# 3_IIP_QuadUART.net
KiCad netlist of a schematic drawn in Altium Designer
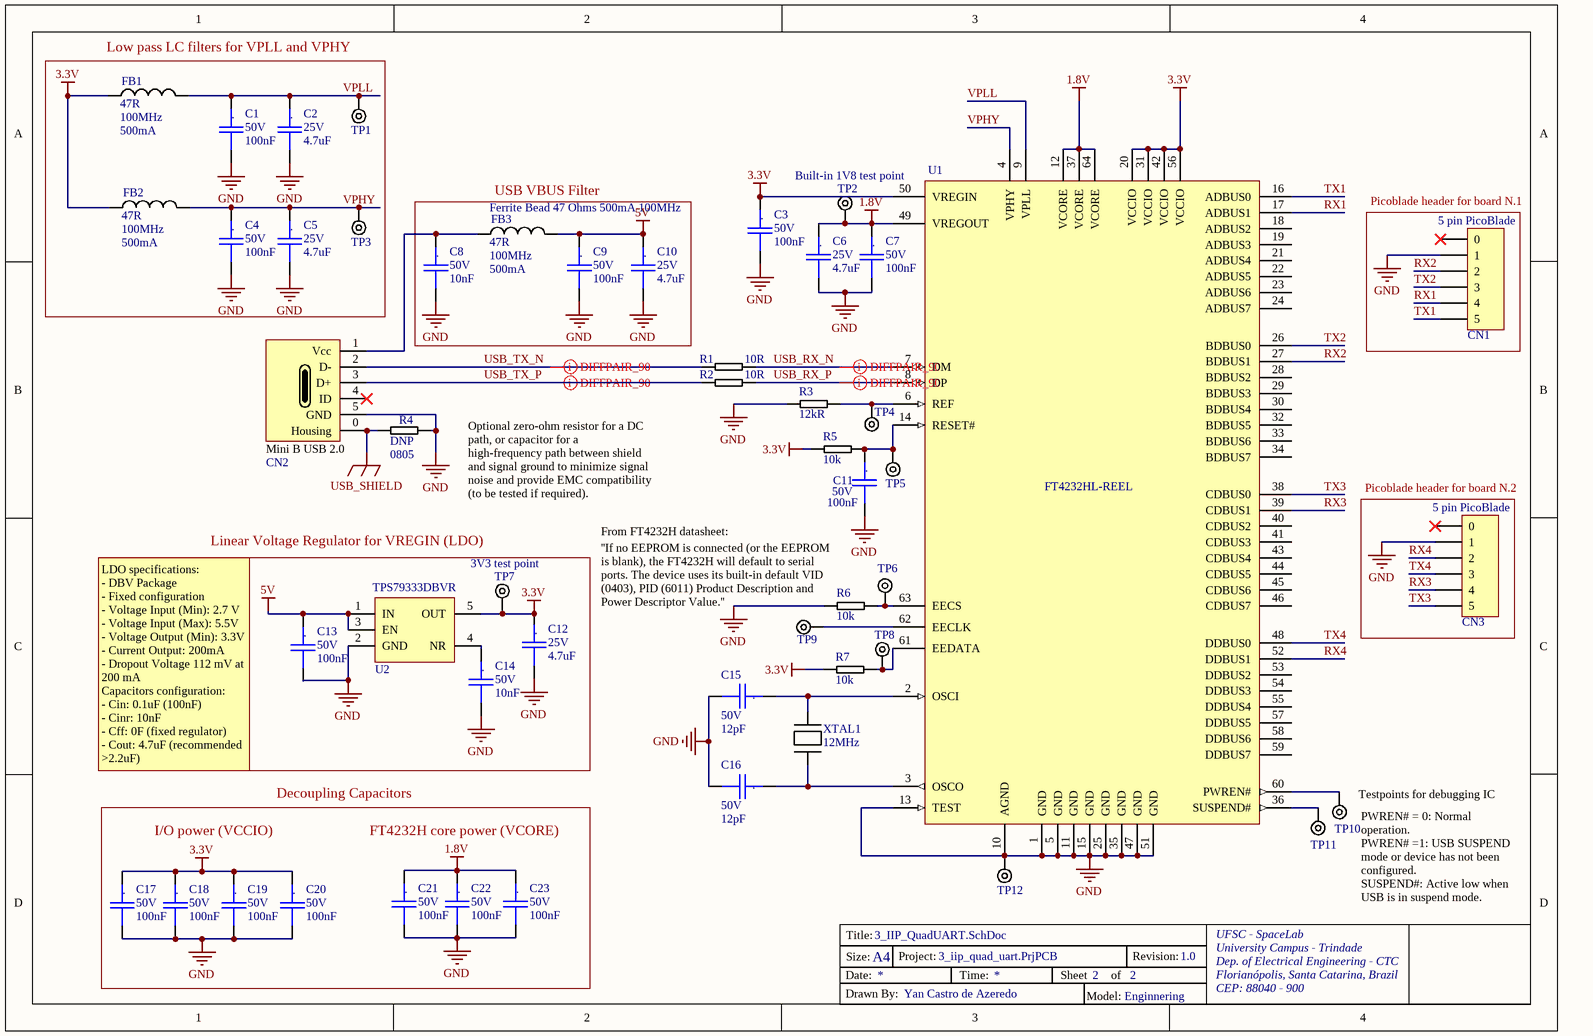
[diagram p0: 3_IIP_QuadUART.SchDoc]

(export (version "E")
  (design (tool "Eeschema 10.0.6"))
  (components
    (comp (ref "C1")
      (value "0.1 uF, 0603 (1608 metric)")
      (footprint "C0603_MD")
      (fields
        (field (name "MANUFACTURER") "TDK")
        (field (name "TOLERANCE") "10%")
        (field (name "VOLTAGE") "50V")
        (field (name "VOLTAGE RATING") "50V")
        (field (name "CAPACITANCE") "100nF")
      )
      (libsource (lib "IB_floripasat2") (part "C1608X7R1H104K080AA"))
    )
    (comp (ref "C2")
      (value "4.7 uF, 0802 (2012 metric)")
      (footprint "C0805_MD")
      (description "Ceramic Capacitor SMD Multilayer, 0805 [2012 Metric], 4.7 uF, 25 V,  10%, X7R, C Series")
      (fields
        (field (name "MANUFACTURER") "TDK")
        (field (name "TOLERANCE") "10%")
        (field (name "VOLTAGE RATING") "25V")
        (field (name "CAPACITANCE") "4.7uF")
      )
      (libsource (lib "IB_floripasat2") (part "C2012X7R1E475K125AB"))
    )
    (comp (ref "C3")
      (value "0.1 uF, 0603 (1608 metric)")
      (footprint "C0603_MD")
      (fields
        (field (name "MANUFACTURER") "TDK")
        (field (name "TOLERANCE") "10%")
        (field (name "VOLTAGE") "50V")
        (field (name "VOLTAGE RATING") "50V")
        (field (name "CAPACITANCE") "100nF")
      )
      (libsource (lib "IB_floripasat2") (part "C1608X7R1H104K080AA"))
    )
    (comp (ref "C4")
      (value "0.1 uF, 0603 (1608 metric)")
      (footprint "C0603_MD")
      (fields
        (field (name "MANUFACTURER") "TDK")
        (field (name "TOLERANCE") "10%")
        (field (name "VOLTAGE") "50V")
        (field (name "VOLTAGE RATING") "50V")
        (field (name "CAPACITANCE") "100nF")
      )
      (libsource (lib "IB_floripasat2") (part "C1608X7R1H104K080AA"))
    )
    (comp (ref "C5")
      (value "4.7 uF, 0802 (2012 metric)")
      (footprint "C0805_MD")
      (description "Ceramic Capacitor SMD Multilayer, 0805 [2012 Metric], 4.7 uF, 25 V,  10%, X7R, C Series")
      (fields
        (field (name "MANUFACTURER") "TDK")
        (field (name "TOLERANCE") "10%")
        (field (name "VOLTAGE RATING") "25V")
        (field (name "CAPACITANCE") "4.7uF")
      )
      (libsource (lib "IB_floripasat2") (part "C2012X7R1E475K125AB"))
    )
    (comp (ref "C6")
      (value "4.7 uF, 0802 (2012 metric)")
      (footprint "C0805_MD")
      (description "Ceramic Capacitor SMD Multilayer, 0805 [2012 Metric], 4.7 uF, 25 V,  10%, X7R, C Series")
      (fields
        (field (name "MANUFACTURER") "TDK")
        (field (name "TOLERANCE") "10%")
        (field (name "VOLTAGE RATING") "25V")
        (field (name "CAPACITANCE") "4.7uF")
      )
      (libsource (lib "IB_floripasat2") (part "C2012X7R1E475K125AB"))
    )
    (comp (ref "C7")
      (value "0.1 uF, 0603 (1608 metric)")
      (footprint "C0603_MD")
      (fields
        (field (name "MANUFACTURER") "TDK")
        (field (name "TOLERANCE") "10%")
        (field (name "VOLTAGE") "50V")
        (field (name "VOLTAGE RATING") "50V")
        (field (name "CAPACITANCE") "100nF")
      )
      (libsource (lib "IB_floripasat2") (part "C1608X7R1H104K080AA"))
    )
    (comp (ref "C8")
      (value "10000 pF, 0805 (2012 metric)")
      (footprint "C0805_MD")
      (fields
        (field (name "MANUFACTURER") "Kyocera AVX")
        (field (name "TOLERANCE") "10%")
        (field (name "MANUFACTURER PART NUMBER") "08055C103KAT4A")
        (field (name "VOLTAGE") "50V")
        (field (name "CAPACITANCE") "10nF")
      )
      (libsource (lib "IB_floripasat2") (part "08055C103KAT4A"))
    )
    (comp (ref "C9")
      (value "0.1 uF, 0603 (1608 metric)")
      (footprint "C0603_MD")
      (fields
        (field (name "MANUFACTURER") "TDK")
        (field (name "TOLERANCE") "10%")
        (field (name "VOLTAGE") "50V")
        (field (name "VOLTAGE RATING") "50V")
        (field (name "CAPACITANCE") "100nF")
      )
      (libsource (lib "IB_floripasat2") (part "C1608X7R1H104K080AA"))
    )
    (comp (ref "C10")
      (value "4.7 uF, 0802 (2012 metric)")
      (footprint "C0805_MD")
      (description "Ceramic Capacitor SMD Multilayer, 0805 [2012 Metric], 4.7 uF, 25 V,  10%, X7R, C Series")
      (fields
        (field (name "MANUFACTURER") "TDK")
        (field (name "TOLERANCE") "10%")
        (field (name "VOLTAGE RATING") "25V")
        (field (name "CAPACITANCE") "4.7uF")
      )
      (libsource (lib "IB_floripasat2") (part "C2012X7R1E475K125AB"))
    )
    (comp (ref "C11")
      (value "0.1 uF, 0603 (1608 metric)")
      (footprint "C0603_MD")
      (fields
        (field (name "MANUFACTURER") "TDK")
        (field (name "TOLERANCE") "10%")
        (field (name "VOLTAGE") "50V")
        (field (name "VOLTAGE RATING") "50V")
        (field (name "CAPACITANCE") "100nF")
      )
      (libsource (lib "IB_floripasat2") (part "C1608X7R1H104K080AA"))
    )
    (comp (ref "C12")
      (value "4.7 uF, 0802 (2012 metric)")
      (footprint "C0805_MD")
      (description "Ceramic Capacitor SMD Multilayer, 0805 [2012 Metric], 4.7 uF, 25 V,  10%, X7R, C Series")
      (fields
        (field (name "MANUFACTURER") "TDK")
        (field (name "TOLERANCE") "10%")
        (field (name "VOLTAGE RATING") "25V")
        (field (name "CAPACITANCE") "4.7uF")
      )
      (libsource (lib "IB_floripasat2") (part "C2012X7R1E475K125AB"))
    )
    (comp (ref "C13")
      (value "0.1 uF, 0603 (1608 metric)")
      (footprint "C0603_MD")
      (fields
        (field (name "MANUFACTURER") "TDK")
        (field (name "TOLERANCE") "10%")
        (field (name "VOLTAGE") "50V")
        (field (name "VOLTAGE RATING") "50V")
        (field (name "CAPACITANCE") "100nF")
      )
      (libsource (lib "IB_floripasat2") (part "C1608X7R1H104K080AA"))
    )
    (comp (ref "C14")
      (value "10000 pF, 0805 (2012 metric)")
      (footprint "C0805_MD")
      (fields
        (field (name "MANUFACTURER") "Kyocera AVX")
        (field (name "TOLERANCE") "10%")
        (field (name "MANUFACTURER PART NUMBER") "08055C103KAT4A")
        (field (name "VOLTAGE") "50V")
        (field (name "CAPACITANCE") "10nF")
      )
      (libsource (lib "IB_floripasat2") (part "08055C103KAT4A"))
    )
    (comp (ref "C15")
      (value "12 pF, 0603 (1608 metric)")
      (footprint "C0603_MD")
      (description "Cap Ceramic 12pF 50VDC C0G 5% SMD 0603 Paper T/R")
      (fields
        (field (name "MANUFACTURER") "Samsung")
        (field (name "MANUFACTURER PART NUMBER") "CL10C120JB8NNNC")
        (field (name "VOLTAGE") "50V")
        (field (name "CAPACITANCE") "12pF")
      )
      (libsource (lib "IB_floripasat2") (part "CL10C120JB8NNNC"))
    )
    (comp (ref "C16")
      (value "12 pF, 0603 (1608 metric)")
      (footprint "C0603_MD")
      (description "Cap Ceramic 12pF 50VDC C0G 5% SMD 0603 Paper T/R")
      (fields
        (field (name "MANUFACTURER") "Samsung")
        (field (name "MANUFACTURER PART NUMBER") "CL10C120JB8NNNC")
        (field (name "VOLTAGE") "50V")
        (field (name "CAPACITANCE") "12pF")
      )
      (libsource (lib "IB_floripasat2") (part "CL10C120JB8NNNC"))
    )
    (comp (ref "C17")
      (value "0.1 uF, 0603 (1608 metric)")
      (footprint "C0603_MD")
      (fields
        (field (name "MANUFACTURER") "TDK")
        (field (name "TOLERANCE") "10%")
        (field (name "VOLTAGE") "50V")
        (field (name "VOLTAGE RATING") "50V")
        (field (name "CAPACITANCE") "100nF")
      )
      (libsource (lib "IB_floripasat2") (part "C1608X7R1H104K080AA"))
    )
    (comp (ref "C18")
      (value "0.1 uF, 0603 (1608 metric)")
      (footprint "C0603_MD")
      (fields
        (field (name "MANUFACTURER") "TDK")
        (field (name "TOLERANCE") "10%")
        (field (name "VOLTAGE") "50V")
        (field (name "VOLTAGE RATING") "50V")
        (field (name "CAPACITANCE") "100nF")
      )
      (libsource (lib "IB_floripasat2") (part "C1608X7R1H104K080AA"))
    )
    (comp (ref "C19")
      (value "0.1 uF, 0603 (1608 metric)")
      (footprint "C0603_MD")
      (fields
        (field (name "MANUFACTURER") "TDK")
        (field (name "TOLERANCE") "10%")
        (field (name "VOLTAGE") "50V")
        (field (name "VOLTAGE RATING") "50V")
        (field (name "CAPACITANCE") "100nF")
      )
      (libsource (lib "IB_floripasat2") (part "C1608X7R1H104K080AA"))
    )
    (comp (ref "C20")
      (value "0.1 uF, 0603 (1608 metric)")
      (footprint "C0603_MD")
      (fields
        (field (name "MANUFACTURER") "TDK")
        (field (name "TOLERANCE") "10%")
        (field (name "VOLTAGE") "50V")
        (field (name "VOLTAGE RATING") "50V")
        (field (name "CAPACITANCE") "100nF")
      )
      (libsource (lib "IB_floripasat2") (part "C1608X7R1H104K080AA"))
    )
    (comp (ref "C21")
      (value "0.1 uF, 0603 (1608 metric)")
      (footprint "C0603_MD")
      (fields
        (field (name "MANUFACTURER") "TDK")
        (field (name "TOLERANCE") "10%")
        (field (name "VOLTAGE") "50V")
        (field (name "VOLTAGE RATING") "50V")
        (field (name "CAPACITANCE") "100nF")
      )
      (libsource (lib "IB_floripasat2") (part "C1608X7R1H104K080AA"))
    )
    (comp (ref "C22")
      (value "0.1 uF, 0603 (1608 metric)")
      (footprint "C0603_MD")
      (fields
        (field (name "MANUFACTURER") "TDK")
        (field (name "TOLERANCE") "10%")
        (field (name "VOLTAGE") "50V")
        (field (name "VOLTAGE RATING") "50V")
        (field (name "CAPACITANCE") "100nF")
      )
      (libsource (lib "IB_floripasat2") (part "C1608X7R1H104K080AA"))
    )
    (comp (ref "C23")
      (value "0.1 uF, 0603 (1608 metric)")
      (footprint "C0603_MD")
      (fields
        (field (name "MANUFACTURER") "TDK")
        (field (name "TOLERANCE") "10%")
        (field (name "VOLTAGE") "50V")
        (field (name "VOLTAGE RATING") "50V")
        (field (name "CAPACITANCE") "100nF")
      )
      (libsource (lib "IB_floripasat2") (part "C1608X7R1H104K080AA"))
    )
    (comp (ref "CN1")
      (value "5 pin PicoBlade")
      (footprint "PICO BLADE 0533980571")
      (description "Wire-To-Board Connector, Vertical, PicoBlade 53398 Series, Surface Mount, Header, 5, 1.25 mm")
      (fields (field (name "MANUFACTURER") "Molex") (field (name "MANUFACTURER PART NUMBER") "53398-0571"))
      (libsource (lib "IB_floripasat2") (part "53398-0571"))
    )
    (comp (ref "CN2")
      (value "Vertical mini B USB 2.0 port")
      (footprint "MINI USB B 180GRAUS WE")
      (fields
        (field (name "MANUFACTURER") "Wurth Electronics")
        (field (name "MANUFACTURER PART NUMBER") "651005136421")
      )
      (libsource (lib "IB_floripasat2") (part "651005136421"))
    )
    (comp (ref "CN3")
      (value "5 pin PicoBlade")
      (footprint "PICO BLADE 0533980571")
      (description "Wire-To-Board Connector, Vertical, PicoBlade 53398 Series, Surface Mount, Header, 5, 1.25 mm")
      (fields (field (name "MANUFACTURER") "Molex") (field (name "MANUFACTURER PART NUMBER") "53398-0571"))
      (libsource (lib "IB_floripasat2") (part "53398-0571"))
    )
    (comp (ref "FB1")
      (value "Ferrite Bead 47 Ohms 500mA 100MHz")
      (footprint "L0603")
      (description "WURTH ELEKTRONIK   742792608   FERRITE BEAD, 0.1 OHM, 0.5A, 0603")
      (fields
        (field (name "MANUFACTURER") "Wurth Electronics")
        (field (name "TOLERANCE") "25%")
        (field (name "IMPEDANCE") "47R")
        (field (name "TEST FREQUENCY") "100MHz")
        (field (name "CURRENT RATING") "500mA")
      )
      (libsource (lib "IB_floripasat2") (part "742792608"))
    )
    (comp (ref "FB2")
      (value "Ferrite Bead 47 Ohms 500mA 100MHz")
      (footprint "L0603")
      (description "WURTH ELEKTRONIK   742792608   FERRITE BEAD, 0.1 OHM, 0.5A, 0603")
      (fields
        (field (name "MANUFACTURER") "Wurth Electronics")
        (field (name "TOLERANCE") "25%")
        (field (name "IMPEDANCE") "47R")
        (field (name "TEST FREQUENCY") "100MHz")
        (field (name "CURRENT RATING") "500mA")
      )
      (libsource (lib "IB_floripasat2") (part "742792608"))
    )
    (comp (ref "FB3")
      (value "Ferrite Bead 47 Ohms 500mA 100MHz")
      (footprint "L0603")
      (description "WURTH ELEKTRONIK   742792608   FERRITE BEAD, 0.1 OHM, 0.5A, 0603")
      (fields
        (field (name "MANUFACTURER") "Wurth Electronics")
        (field (name "TOLERANCE") "25%")
        (field (name "IMPEDANCE") "47R")
        (field (name "TEST FREQUENCY") "100MHz")
        (field (name "CURRENT RATING") "500mA")
      )
      (libsource (lib "IB_floripasat2") (part "742792608"))
    )
    (comp (ref "R1")
      (value "RES 10 ohms (0603)")
      (footprint "R0603_MD")
      (description "YAGEO (PHYCOMP) - RC0603FR-0710RL - RES, THICK FILM, 10R, 1%, 0.1W, 0603")
      (fields
        (field (name "MANUFACTURER") "Yageo")
        (field (name "TOLERANCE") "1%")
        (field (name "RESISTANCE") "10R")
      )
      (libsource (lib "IB_floripasat2") (part "RC0603FR-0710RL"))
    )
    (comp (ref "R2")
      (value "RES 10 ohms (0603)")
      (footprint "R0603_MD")
      (description "YAGEO (PHYCOMP) - RC0603FR-0710RL - RES, THICK FILM, 10R, 1%, 0.1W, 0603")
      (fields
        (field (name "MANUFACTURER") "Yageo")
        (field (name "TOLERANCE") "1%")
        (field (name "RESISTANCE") "10R")
      )
      (libsource (lib "IB_floripasat2") (part "RC0603FR-0710RL"))
    )
    (comp (ref "R3")
      (value "RES 12K ohms (0805)")
      (footprint "R0805_MD")
      (description "Resistor, SMT, 0805, 12K Ohm, +/-1%, +/-100ppm, Thk Film, T/R Marked")
      (fields
        (field (name "MANUFACTURER") "Stackpole Electronics")
        (field (name "MANUFACTURER PART NUMBER") "RMCF0805FT12K0")
        (field (name "RESISTANCE") "12kR")
      )
      (libsource (lib "IB_floripasat2") (part "RMCF0805FT12K0"))
    )
    (comp (ref "R4")
      (value "DNP")
      (footprint "R0805_MD")
      (fields
        (field (name "MANUFACTURER") "Vishay")
        (field (name "TOLERANCE") "1%")
        (field (name "MANUFACTURER PART NUMBER") "CRCW08050000Z0EA")
        (field (name "CASE/PACKAGE") "0805")
      )
      (libsource (lib "IB_floripasat2") (part "CRCW08050000Z0EA"))
    )
    (comp (ref "R5")
      (value "10k")
      (footprint "R0805_MD")
      (description "RES 10.0K OHM 1/8W 1% 0805 SMD")
      (fields (field (name "MANUFACTURER") "Vishay Dale") (field (name "TOLERANCE") "1%"))
      (libsource (lib "IB_floripasat2") (part "CRCW080510K0FKEA"))
    )
    (comp (ref "R6")
      (value "10k")
      (footprint "R0805_MD")
      (description "RES 10.0K OHM 1/8W 1% 0805 SMD")
      (fields (field (name "MANUFACTURER") "Vishay Dale") (field (name "TOLERANCE") "1%"))
      (libsource (lib "IB_floripasat2") (part "CRCW080510K0FKEA"))
    )
    (comp (ref "R7")
      (value "10k")
      (footprint "R0805_MD")
      (description "RES 10.0K OHM 1/8W 1% 0805 SMD")
      (fields (field (name "MANUFACTURER") "Vishay Dale") (field (name "TOLERANCE") "1%"))
      (libsource (lib "IB_floripasat2") (part "CRCW080510K0FKEA"))
    )
    (comp (ref "TP1")
      (value "DNP")
      (footprint "TEST POINT PTH")
      (description "TEST POINT PAD")
      (libsource (lib "IB_floripasat2") (part "Test Point PTH"))
    )
    (comp (ref "TP2")
      (value "DNP")
      (footprint "TEST POINT PTH")
      (description "TEST POINT PAD")
      (libsource (lib "IB_floripasat2") (part "Test Point PTH"))
    )
    (comp (ref "TP3")
      (value "DNP")
      (footprint "TEST POINT PTH")
      (description "TEST POINT PAD")
      (libsource (lib "IB_floripasat2") (part "Test Point PTH"))
    )
    (comp (ref "TP4")
      (value "DNP")
      (footprint "TEST POINT PTH")
      (description "TEST POINT PAD")
      (libsource (lib "IB_floripasat2") (part "Test Point PTH"))
    )
    (comp (ref "TP5")
      (value "DNP")
      (footprint "TEST POINT PTH")
      (description "TEST POINT PAD")
      (libsource (lib "IB_floripasat2") (part "Test Point PTH"))
    )
    (comp (ref "TP6")
      (value "DNP")
      (footprint "TEST POINT PTH")
      (description "TEST POINT PAD")
      (libsource (lib "IB_floripasat2") (part "Test Point PTH"))
    )
    (comp (ref "TP7")
      (value "DNP")
      (footprint "TEST POINT PTH")
      (description "TEST POINT PAD")
      (libsource (lib "IB_floripasat2") (part "Test Point PTH"))
    )
    (comp (ref "TP8")
      (value "DNP")
      (footprint "TEST POINT PTH")
      (description "TEST POINT PAD")
      (libsource (lib "IB_floripasat2") (part "Test Point PTH"))
    )
    (comp (ref "TP9")
      (value "DNP")
      (footprint "TEST POINT PTH")
      (description "TEST POINT PAD")
      (libsource (lib "IB_floripasat2") (part "Test Point PTH"))
    )
    (comp (ref "TP10")
      (value "DNP")
      (footprint "TEST POINT PTH")
      (description "TEST POINT PAD")
      (libsource (lib "IB_floripasat2") (part "Test Point PTH"))
    )
    (comp (ref "TP11")
      (value "DNP")
      (footprint "TEST POINT PTH")
      (description "TEST POINT PAD")
      (libsource (lib "IB_floripasat2") (part "Test Point PTH"))
    )
    (comp (ref "TP12")
      (value "DNP")
      (footprint "TEST POINT PTH")
      (description "TEST POINT PAD")
      (libsource (lib "IB_floripasat2") (part "Test Point PTH"))
    )
    (comp (ref "U1")
      (value "FT4232HL-REEL")
      (footprint "LQFP-64")
      (description "FTDI - FT4232HL-REEL - USB-UART/MPSSE, 4232, QUAD, 64LQFP")
      (fields (field (name "MANUFACTURER") "FTDI"))
      (libsource (lib "IB_floripasat2") (part "FT4232HL-REEL"))
    )
    (comp (ref "U2")
      (value "TPS79333DBVR")
      (footprint "SOT23-5")
      (description "TEXAS INSTRUMENTS - TPS79333DBVR - IC, V REG, LINEAR, 0.2A, SOT-23-5")
      (fields (field (name "MANUFACTURER") "Texas Instruments"))
      (libsource (lib "IB_floripasat2") (part "TPS79333DBVR"))
    )
    (comp (ref "XTAL1")
      (value "12.000MHz 12pF")
      (footprint "TXC 7A Series")
      (description "Crystals 12.000MHz 30ppm 12pF -40C to 85C")
      (fields
        (field (name "MANUFACTURER") "TXC")
        (field (name "TOLERANCE") "30ppm")
        (field (name "FREQUENCY") "12MHz")
      )
      (libsource (lib "IB_floripasat2") (part "AA-12.000MAGE-T"))
    )
  )
  (nets
    (net (code "1") (name "/RX1") (class "Default")
      (node (ref "CN1") (pin "4") (pinfunction "4_4") (pintype "passive"))
      (node (ref "U1") (pin "17") (pinfunction "ADBUS1_17") (pintype "passive"))
    )
    (net (code "2") (name "/RX2") (class "Default")
      (node (ref "CN1") (pin "2") (pinfunction "2_2") (pintype "passive"))
      (node (ref "U1") (pin "27") (pinfunction "BDBUS1_27") (pintype "passive"))
    )
    (net (code "3") (name "/RX3") (class "Default")
      (node (ref "CN3") (pin "4") (pinfunction "4_4") (pintype "passive"))
      (node (ref "U1") (pin "39") (pinfunction "CDBUS1_39") (pintype "passive"))
    )
    (net (code "4") (name "/RX4") (class "Default")
      (node (ref "CN3") (pin "2") (pinfunction "2_2") (pintype "passive"))
      (node (ref "U1") (pin "52") (pinfunction "DDBUS1_52") (pintype "passive"))
    )
    (net (code "5") (name "/TX1") (class "Default")
      (node (ref "CN1") (pin "5") (pinfunction "5_5") (pintype "passive"))
      (node (ref "U1") (pin "16") (pinfunction "ADBUS0_16") (pintype "passive"))
    )
    (net (code "6") (name "/TX2") (class "Default")
      (node (ref "CN1") (pin "3") (pinfunction "3_3") (pintype "passive"))
      (node (ref "U1") (pin "26") (pinfunction "BDBUS0_26") (pintype "passive"))
    )
    (net (code "7") (name "/TX3") (class "Default")
      (node (ref "CN3") (pin "5") (pinfunction "5_5") (pintype "passive"))
      (node (ref "U1") (pin "38") (pinfunction "CDBUS0_38") (pintype "passive"))
    )
    (net (code "8") (name "/TX4") (class "Default")
      (node (ref "CN3") (pin "3") (pinfunction "3_3") (pintype "passive"))
      (node (ref "U1") (pin "48") (pinfunction "DDBUS0_48") (pintype "passive"))
    )
    (net (code "9") (name "/USB_RX_N") (class "Default")
      (node (ref "R1") (pin "2") (pinfunction "2_2") (pintype "passive"))
      (node (ref "U1") (pin "7") (pinfunction "DM_7") (pintype "bidirectional"))
    )
    (net (code "10") (name "/USB_RX_P") (class "Default")
      (node (ref "R2") (pin "2") (pinfunction "2_2") (pintype "passive"))
      (node (ref "U1") (pin "8") (pinfunction "DP_8") (pintype "bidirectional"))
    )
    (net (code "11") (name "/USB_TX_N") (class "Default")
      (node (ref "CN2") (pin "2") (pinfunction "D-_2") (pintype "passive"))
      (node (ref "R1") (pin "1") (pinfunction "1_1") (pintype "passive"))
    )
    (net (code "12") (name "/USB_TX_P") (class "Default")
      (node (ref "CN2") (pin "3") (pinfunction "D+_3") (pintype "passive"))
      (node (ref "R2") (pin "1") (pinfunction "1_1") (pintype "passive"))
    )
    (net (code "13") (name "/VPHY") (class "Default")
      (node (ref "C4") (pin "1") (pinfunction "1_1") (pintype "passive"))
      (node (ref "C5") (pin "1") (pinfunction "1_1") (pintype "passive"))
      (node (ref "FB2") (pin "2") (pinfunction "2_2") (pintype "passive"))
      (node (ref "TP3") (pin "1") (pinfunction "1_1") (pintype "passive"))
      (node (ref "U1") (pin "4") (pinfunction "VPHY_4") (pintype "power_in"))
    )
    (net (code "14") (name "/VPLL") (class "Default")
      (node (ref "C1") (pin "1") (pinfunction "1_1") (pintype "passive"))
      (node (ref "C2") (pin "1") (pinfunction "1_1") (pintype "passive"))
      (node (ref "FB1") (pin "2") (pinfunction "2_2") (pintype "passive"))
      (node (ref "TP1") (pin "1") (pinfunction "1_1") (pintype "passive"))
      (node (ref "U1") (pin "9") (pinfunction "VPLL_9") (pintype "power_in"))
    )
    (net (code "15") (name "1.8V") (class "Default")
      (node (ref "C21") (pin "1") (pinfunction "1_1") (pintype "passive"))
      (node (ref "C22") (pin "1") (pinfunction "1_1") (pintype "passive"))
      (node (ref "C23") (pin "1") (pinfunction "1_1") (pintype "passive"))
      (node (ref "C6") (pin "1") (pinfunction "1_1") (pintype "passive"))
      (node (ref "C7") (pin "1") (pinfunction "1_1") (pintype "passive"))
      (node (ref "TP2") (pin "1") (pinfunction "1_1") (pintype "passive"))
      (node (ref "U1") (pin "12") (pinfunction "VCORE_12") (pintype "power_in"))
      (node (ref "U1") (pin "37") (pinfunction "VCORE_37") (pintype "power_in"))
      (node (ref "U1") (pin "49") (pinfunction "VREGOUT_49") (pintype "passive"))
      (node (ref "U1") (pin "64") (pinfunction "VCORE_64") (pintype "power_in"))
    )
    (net (code "16") (name "3.3V") (class "Default")
      (node (ref "C12") (pin "1") (pinfunction "1_1") (pintype "passive"))
      (node (ref "C17") (pin "1") (pinfunction "1_1") (pintype "passive"))
      (node (ref "C18") (pin "1") (pinfunction "1_1") (pintype "passive"))
      (node (ref "C19") (pin "1") (pinfunction "1_1") (pintype "passive"))
      (node (ref "C20") (pin "1") (pinfunction "1_1") (pintype "passive"))
      (node (ref "C3") (pin "1") (pinfunction "1_1") (pintype "passive"))
      (node (ref "FB1") (pin "1") (pinfunction "1_1") (pintype "passive"))
      (node (ref "FB2") (pin "1") (pinfunction "1_1") (pintype "passive"))
      (node (ref "R5") (pin "1") (pinfunction "1_1") (pintype "passive"))
      (node (ref "R7") (pin "1") (pinfunction "1_1") (pintype "passive"))
      (node (ref "TP7") (pin "1") (pinfunction "1_1") (pintype "passive"))
      (node (ref "U1") (pin "20") (pinfunction "VCCIO_20") (pintype "power_in"))
      (node (ref "U1") (pin "31") (pinfunction "VCCIO_31") (pintype "power_in"))
      (node (ref "U1") (pin "42") (pinfunction "VCCIO_42") (pintype "power_in"))
      (node (ref "U1") (pin "50") (pinfunction "VREGIN_50") (pintype "passive"))
      (node (ref "U1") (pin "56") (pinfunction "VCCIO_56") (pintype "power_in"))
      (node (ref "U2") (pin "5") (pinfunction "OUT_5") (pintype "passive"))
    )
    (net (code "17") (name "5V") (class "Default")
      (node (ref "C10") (pin "1") (pinfunction "1_1") (pintype "passive"))
      (node (ref "C13") (pin "1") (pinfunction "1_1") (pintype "passive"))
      (node (ref "C9") (pin "1") (pinfunction "1_1") (pintype "passive"))
      (node (ref "FB3") (pin "2") (pinfunction "2_2") (pintype "passive"))
      (node (ref "U2") (pin "1") (pinfunction "IN_1") (pintype "passive"))
      (node (ref "U2") (pin "3") (pinfunction "EN_3") (pintype "passive"))
    )
    (net (code "18") (name "GND") (class "Default")
      (node (ref "C1") (pin "2") (pinfunction "2_2") (pintype "passive"))
      (node (ref "C10") (pin "2") (pinfunction "2_2") (pintype "passive"))
      (node (ref "C11") (pin "2") (pinfunction "2_2") (pintype "passive"))
      (node (ref "C12") (pin "2") (pinfunction "2_2") (pintype "passive"))
      (node (ref "C13") (pin "2") (pinfunction "2_2") (pintype "passive"))
      (node (ref "C14") (pin "2") (pinfunction "2_2") (pintype "passive"))
      (node (ref "C15") (pin "2") (pinfunction "2_2") (pintype "passive"))
      (node (ref "C16") (pin "2") (pinfunction "2_2") (pintype "passive"))
      (node (ref "C17") (pin "2") (pinfunction "2_2") (pintype "passive"))
      (node (ref "C18") (pin "2") (pinfunction "2_2") (pintype "passive"))
      (node (ref "C19") (pin "2") (pinfunction "2_2") (pintype "passive"))
      (node (ref "C2") (pin "2") (pinfunction "2_2") (pintype "passive"))
      (node (ref "C20") (pin "2") (pinfunction "2_2") (pintype "passive"))
      (node (ref "C21") (pin "2") (pinfunction "2_2") (pintype "passive"))
      (node (ref "C22") (pin "2") (pinfunction "2_2") (pintype "passive"))
      (node (ref "C23") (pin "2") (pinfunction "2_2") (pintype "passive"))
      (node (ref "C3") (pin "2") (pinfunction "2_2") (pintype "passive"))
      (node (ref "C4") (pin "2") (pinfunction "2_2") (pintype "passive"))
      (node (ref "C5") (pin "2") (pinfunction "2_2") (pintype "passive"))
      (node (ref "C6") (pin "2") (pinfunction "2_2") (pintype "passive"))
      (node (ref "C7") (pin "2") (pinfunction "2_2") (pintype "passive"))
      (node (ref "C8") (pin "2") (pinfunction "2_2") (pintype "passive"))
      (node (ref "C9") (pin "2") (pinfunction "2_2") (pintype "passive"))
      (node (ref "CN1") (pin "1") (pinfunction "1_1") (pintype "passive"))
      (node (ref "CN2") (pin "5") (pinfunction "GND_5") (pintype "passive"))
      (node (ref "CN3") (pin "1") (pinfunction "1_1") (pintype "passive"))
      (node (ref "R3") (pin "1") (pinfunction "1_1") (pintype "passive"))
      (node (ref "R4") (pin "2") (pinfunction "2_2") (pintype "passive"))
      (node (ref "R6") (pin "1") (pinfunction "1_1") (pintype "passive"))
      (node (ref "TP12") (pin "1") (pinfunction "1_1") (pintype "passive"))
      (node (ref "U1") (pin "1") (pinfunction "GND_1") (pintype "passive"))
      (node (ref "U1") (pin "10") (pinfunction "AGND_10") (pintype "passive"))
      (node (ref "U1") (pin "11") (pinfunction "GND_11") (pintype "passive"))
      (node (ref "U1") (pin "13") (pinfunction "TEST_13") (pintype "input"))
      (node (ref "U1") (pin "15") (pinfunction "GND_15") (pintype "passive"))
      (node (ref "U1") (pin "25") (pinfunction "GND_25") (pintype "passive"))
      (node (ref "U1") (pin "35") (pinfunction "GND_35") (pintype "passive"))
      (node (ref "U1") (pin "47") (pinfunction "GND_47") (pintype "passive"))
      (node (ref "U1") (pin "5") (pinfunction "GND_5") (pintype "passive"))
      (node (ref "U1") (pin "51") (pinfunction "GND_51") (pintype "passive"))
      (node (ref "U2") (pin "2") (pinfunction "GND_2") (pintype "passive"))
    )
    (net (code "19") (name "Net-(CN2-Vcc)") (class "Default")
      (node (ref "C8") (pin "1") (pinfunction "1_1") (pintype "passive"))
      (node (ref "CN2") (pin "1") (pinfunction "Vcc_1") (pintype "passive"))
      (node (ref "FB3") (pin "1") (pinfunction "1_1") (pintype "passive"))
    )
    (net (code "20") (name "Net-(U1-EECLK)") (class "Default")
      (node (ref "TP9") (pin "1") (pinfunction "1_1") (pintype "passive"))
      (node (ref "U1") (pin "62") (pinfunction "EECLK_62") (pintype "passive"))
    )
    (net (code "21") (name "Net-(U1-EECS)") (class "Default")
      (node (ref "R6") (pin "2") (pinfunction "2_2") (pintype "passive"))
      (node (ref "TP6") (pin "1") (pinfunction "1_1") (pintype "passive"))
      (node (ref "U1") (pin "63") (pinfunction "EECS_63") (pintype "passive"))
    )
    (net (code "22") (name "Net-(U1-EEDATA)") (class "Default")
      (node (ref "R7") (pin "2") (pinfunction "2_2") (pintype "passive"))
      (node (ref "TP8") (pin "1") (pinfunction "1_1") (pintype "passive"))
      (node (ref "U1") (pin "61") (pinfunction "EEDATA_61") (pintype "passive"))
    )
    (net (code "23") (name "Net-(U1-OSCI)") (class "Default")
      (node (ref "C15") (pin "1") (pinfunction "1_1") (pintype "passive"))
      (node (ref "U1") (pin "2") (pinfunction "OSCI_2") (pintype "input"))
      (node (ref "XTAL1") (pin "1") (pinfunction "1_1") (pintype "passive"))
    )
    (net (code "24") (name "Net-(U1-OSCO)") (class "Default")
      (node (ref "C16") (pin "1") (pinfunction "1_1") (pintype "passive"))
      (node (ref "U1") (pin "3") (pinfunction "OSCO_3") (pintype "output"))
      (node (ref "XTAL1") (pin "2") (pinfunction "2_2") (pintype "passive"))
    )
    (net (code "25") (name "Net-(U1-PWREN#)") (class "Default")
      (node (ref "TP10") (pin "1") (pinfunction "1_1") (pintype "passive"))
      (node (ref "U1") (pin "60") (pinfunction "PWREN#_60") (pintype "output"))
    )
    (net (code "26") (name "Net-(U1-REF)") (class "Default")
      (node (ref "R3") (pin "2") (pinfunction "2_2") (pintype "passive"))
      (node (ref "TP4") (pin "1") (pinfunction "1_1") (pintype "passive"))
      (node (ref "U1") (pin "6") (pinfunction "REF_6") (pintype "input"))
    )
    (net (code "27") (name "Net-(U1-RESET#)") (class "Default")
      (node (ref "C11") (pin "1") (pinfunction "1_1") (pintype "passive"))
      (node (ref "R5") (pin "2") (pinfunction "2_2") (pintype "passive"))
      (node (ref "TP5") (pin "1") (pinfunction "1_1") (pintype "passive"))
      (node (ref "U1") (pin "14") (pinfunction "RESET#_14") (pintype "input"))
    )
    (net (code "28") (name "Net-(U1-SUSPEND#)") (class "Default")
      (node (ref "TP11") (pin "1") (pinfunction "1_1") (pintype "passive"))
      (node (ref "U1") (pin "36") (pinfunction "SUSPEND#_36") (pintype "output"))
    )
    (net (code "29") (name "Net-(U2-NR)") (class "Default")
      (node (ref "C14") (pin "1") (pinfunction "1_1") (pintype "passive"))
      (node (ref "U2") (pin "4") (pinfunction "NR_4") (pintype "passive"))
    )
    (net (code "30") (name "USB_SHIELD") (class "Default")
      (node (ref "CN2") (pin "0") (pinfunction "Housing_0") (pintype "passive"))
      (node (ref "R4") (pin "1") (pinfunction "1_1") (pintype "passive"))
    )
    (net (code "31") (name "unconnected-(CN1-Pad0)") (class "Default")
      (node (ref "CN1") (pin "0") (pinfunction "0_0") (pintype "passive+no_connect"))
    )
    (net (code "32") (name "unconnected-(CN2-ID-Pad4)") (class "Default")
      (node (ref "CN2") (pin "4") (pinfunction "ID_4") (pintype "passive+no_connect"))
    )
    (net (code "33") (name "unconnected-(CN3-Pad0)") (class "Default")
      (node (ref "CN3") (pin "0") (pinfunction "0_0") (pintype "passive+no_connect"))
    )
    (net (code "34") (name "unconnected-(U1-ADBUS2-Pad18)") (class "Default")
      (node (ref "U1") (pin "18") (pinfunction "ADBUS2_18") (pintype "passive"))
    )
    (net (code "35") (name "unconnected-(U1-ADBUS3-Pad19)") (class "Default")
      (node (ref "U1") (pin "19") (pinfunction "ADBUS3_19") (pintype "passive"))
    )
    (net (code "36") (name "unconnected-(U1-ADBUS4-Pad21)") (class "Default")
      (node (ref "U1") (pin "21") (pinfunction "ADBUS4_21") (pintype "passive"))
    )
    (net (code "37") (name "unconnected-(U1-ADBUS5-Pad22)") (class "Default")
      (node (ref "U1") (pin "22") (pinfunction "ADBUS5_22") (pintype "passive"))
    )
    (net (code "38") (name "unconnected-(U1-ADBUS6-Pad23)") (class "Default")
      (node (ref "U1") (pin "23") (pinfunction "ADBUS6_23") (pintype "passive"))
    )
    (net (code "39") (name "unconnected-(U1-ADBUS7-Pad24)") (class "Default")
      (node (ref "U1") (pin "24") (pinfunction "ADBUS7_24") (pintype "passive"))
    )
    (net (code "40") (name "unconnected-(U1-BDBUS2-Pad28)") (class "Default")
      (node (ref "U1") (pin "28") (pinfunction "BDBUS2_28") (pintype "passive"))
    )
    (net (code "41") (name "unconnected-(U1-BDBUS3-Pad29)") (class "Default")
      (node (ref "U1") (pin "29") (pinfunction "BDBUS3_29") (pintype "passive"))
    )
    (net (code "42") (name "unconnected-(U1-BDBUS4-Pad30)") (class "Default")
      (node (ref "U1") (pin "30") (pinfunction "BDBUS4_30") (pintype "passive"))
    )
    (net (code "43") (name "unconnected-(U1-BDBUS5-Pad32)") (class "Default")
      (node (ref "U1") (pin "32") (pinfunction "BDBUS5_32") (pintype "passive"))
    )
    (net (code "44") (name "unconnected-(U1-BDBUS6-Pad33)") (class "Default")
      (node (ref "U1") (pin "33") (pinfunction "BDBUS6_33") (pintype "passive"))
    )
    (net (code "45") (name "unconnected-(U1-BDBUS7-Pad34)") (class "Default")
      (node (ref "U1") (pin "34") (pinfunction "BDBUS7_34") (pintype "passive"))
    )
    (net (code "46") (name "unconnected-(U1-CDBUS2-Pad40)") (class "Default")
      (node (ref "U1") (pin "40") (pinfunction "CDBUS2_40") (pintype "passive"))
    )
    (net (code "47") (name "unconnected-(U1-CDBUS3-Pad41)") (class "Default")
      (node (ref "U1") (pin "41") (pinfunction "CDBUS3_41") (pintype "passive"))
    )
    (net (code "48") (name "unconnected-(U1-CDBUS4-Pad43)") (class "Default")
      (node (ref "U1") (pin "43") (pinfunction "CDBUS4_43") (pintype "passive"))
    )
    (net (code "49") (name "unconnected-(U1-CDBUS5-Pad44)") (class "Default")
      (node (ref "U1") (pin "44") (pinfunction "CDBUS5_44") (pintype "passive"))
    )
    (net (code "50") (name "unconnected-(U1-CDBUS6-Pad45)") (class "Default")
      (node (ref "U1") (pin "45") (pinfunction "CDBUS6_45") (pintype "passive"))
    )
    (net (code "51") (name "unconnected-(U1-CDBUS7-Pad46)") (class "Default")
      (node (ref "U1") (pin "46") (pinfunction "CDBUS7_46") (pintype "passive"))
    )
    (net (code "52") (name "unconnected-(U1-DDBUS2-Pad53)") (class "Default")
      (node (ref "U1") (pin "53") (pinfunction "DDBUS2_53") (pintype "passive"))
    )
    (net (code "53") (name "unconnected-(U1-DDBUS3-Pad54)") (class "Default")
      (node (ref "U1") (pin "54") (pinfunction "DDBUS3_54") (pintype "passive"))
    )
    (net (code "54") (name "unconnected-(U1-DDBUS4-Pad55)") (class "Default")
      (node (ref "U1") (pin "55") (pinfunction "DDBUS4_55") (pintype "passive"))
    )
    (net (code "55") (name "unconnected-(U1-DDBUS5-Pad57)") (class "Default")
      (node (ref "U1") (pin "57") (pinfunction "DDBUS5_57") (pintype "passive"))
    )
    (net (code "56") (name "unconnected-(U1-DDBUS6-Pad58)") (class "Default")
      (node (ref "U1") (pin "58") (pinfunction "DDBUS6_58") (pintype "passive"))
    )
    (net (code "57") (name "unconnected-(U1-DDBUS7-Pad59)") (class "Default")
      (node (ref "U1") (pin "59") (pinfunction "DDBUS7_59") (pintype "passive"))
    )
  )
)
